# Power.net
KiCad netlist of a schematic drawn in Altium Designer
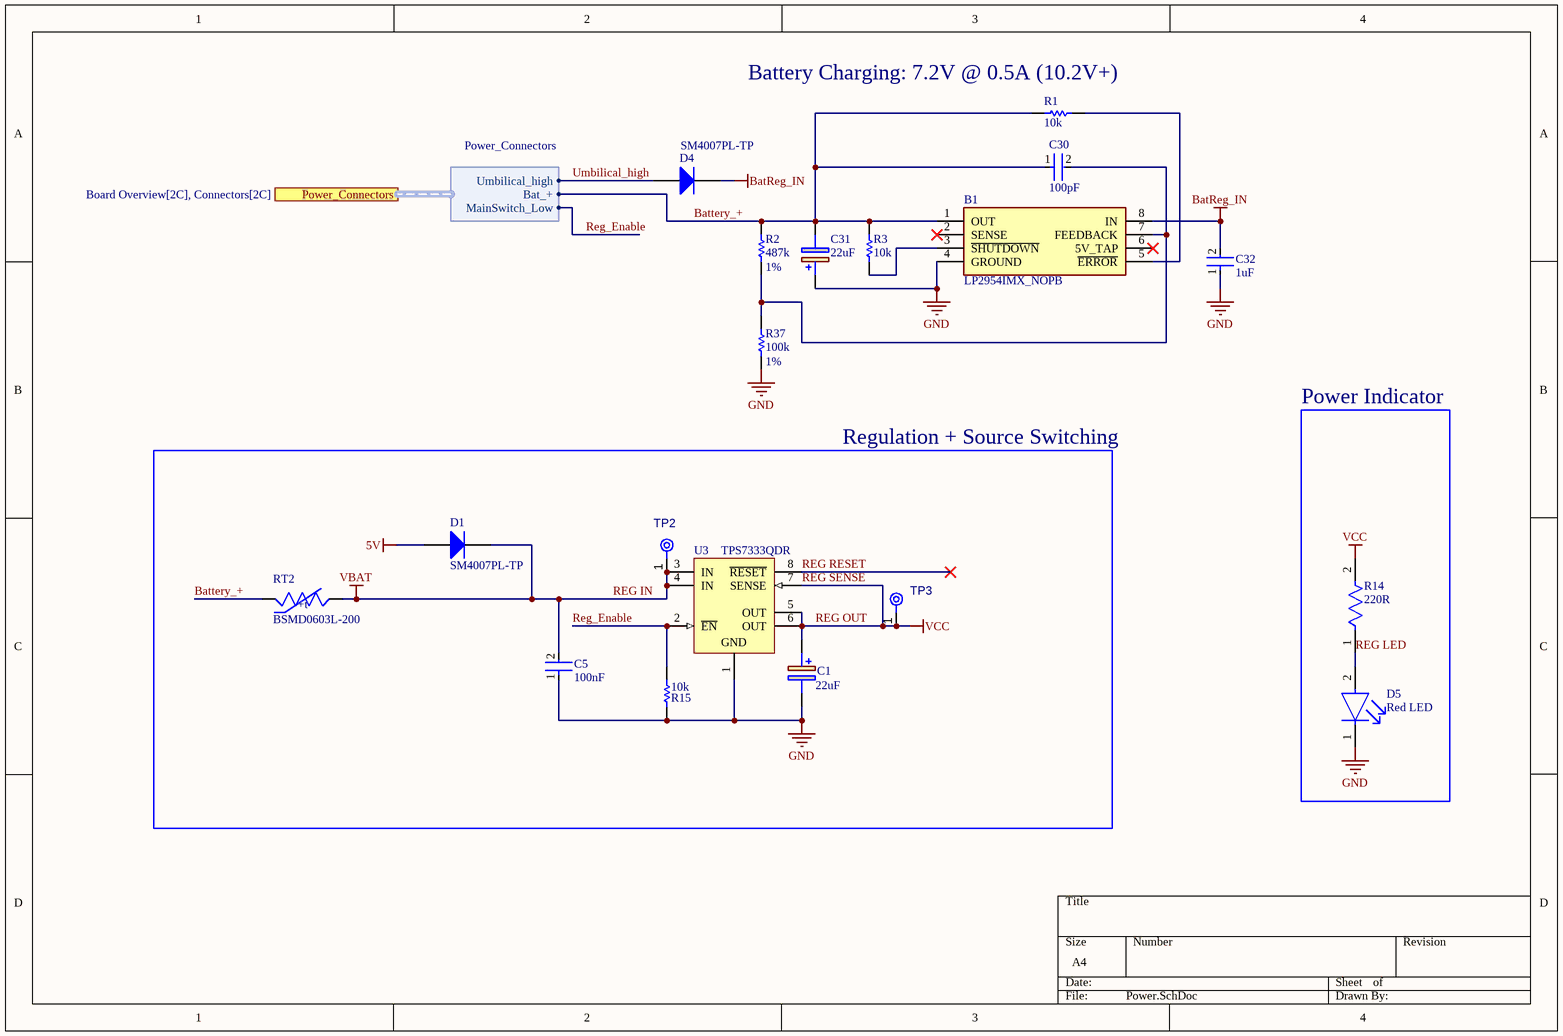
[diagram p0: Power.SchDoc]

(export (version "E")
  (design (tool "Eeschema 10.0.6"))
  (components
    (comp (ref "B1")
      (value "LP2954IMX_NOPB")
      (footprint "SOIC127P600X175-8N")
      (description "5V and Adjustable Micropower LDOs")
      (fields
        (field (name "MOUSER PART NUMBER") "926-LP2954IMX/NOPB")
        (field (name "MANUFACTURER_PART_NUMBER") "LP2954IMX/NOPB")
      )
      (libsource (lib "StrathSEDS") (part "LP2954IMX_NOPB"))
    )
    (comp (ref "C1")
      (value "TPSB226K010R0500")
      (footprint "CAPPM3528X210N")
      (description "AVX Electrolytic Capacitor 22uF 10V dc Electrolytic Solid +/-10% Tolerance TPS Series")
      (fields
        (field (name "LCSC PART #") "C400102")
        (field (name "MOUSER PART NUMBER") "581-TPSB226K010R0500")
        (field (name "CAPACITANCE") "22uF")
      )
      (libsource (lib "StrathSEDS") (part "TPSB226K010R0500"))
    )
    (comp (ref "C5")
      (value "100nF")
      (footprint "FP-0603-L_1_6_0_15-W_0_81-IPC_C")
      (description "Generic 0603 Capacitor")
      (fields (field (name "LCSC PART #") "C14663") (field (name "TOLERANCE") "10%"))
      (libsource (lib "StrathSEDS") (part "02cd4be3c70576c341d710602a673aa"))
    )
    (comp (ref "C30")
      (value "100pF")
      (footprint "FP-0603-L_1_6_0_15-W_0_81-IPC_C")
      (description "Generic 0603 Capacitor")
      (fields (field (name "LCSC PART #") "C14858") (field (name "TOLERANCE") "10%"))
      (libsource (lib "StrathSEDS") (part "02cd4be3c70576c341d710602a673aa"))
    )
    (comp (ref "C31")
      (value "TPSB226K010R0500")
      (footprint "CAPPM3528X210N")
      (description "AVX Electrolytic Capacitor 22uF 10V dc Electrolytic Solid +/-10% Tolerance TPS Series")
      (fields
        (field (name "LCSC PART #") "C400102")
        (field (name "MOUSER PART NUMBER") "581-TPSB226K010R0500")
        (field (name "CAPACITANCE") "22uF")
      )
      (libsource (lib "") (part "TPSB226K010R0500_1"))
    )
    (comp (ref "C32")
      (value "1uF")
      (footprint "FP-0603-L_1_6_0_15-W_0_81-IPC_C")
      (description "Generic 0603 Capacitor")
      (fields (field (name "LCSC PART #") "C15849") (field (name "TOLERANCE") "10%"))
      (libsource (lib "StrathSEDS") (part "02cd4be3c70576c341d710602a673aa"))
    )
    (comp (ref "D1")
      (value "SM4007PL-TP")
      (footprint "MCC-SOD-123FL_V")
      (description "DIODE GEN PURP 1KV 1A SOD123FL")
      (fields (field (name "LCSC PART #") "C64898"))
      (libsource (lib "StrathSEDS") (part "D-AK-2"))
    )
    (comp (ref "D4")
      (value "SM4007PL-TP")
      (footprint "MCC-SOD-123FL_V")
      (description "DIODE GEN PURP 1KV 1A SOD123FL")
      (fields (field (name "LCSC PART #") "C64898"))
      (libsource (lib "StrathSEDS") (part "D-AK-2"))
    )
    (comp (ref "D5")
      (value "Red LED")
      (footprint "FP-LTST-C190GKT-MFG")
      (description "SZYY0603R")
      (fields (field (name "LCSC PART #") "C434419"))
      (libsource (lib "StrathSEDS Mach 22") (part "8706943c75ba83719d021d2fdc84c58"))
    )
    (comp (ref "R1")
      (value "10k")
      (footprint "RESC1609X50X30ML8T20")
      (description "Generic 0603 Resistor")
      (fields (field (name "LCSC PART #") "C25804") (field (name "TOLERANCE") "0%"))
      (libsource (lib "StrathSEDS") (part "RES-2"))
    )
    (comp (ref "R2")
      (value "487k")
      (footprint "RESC1609X50X30ML8T20")
      (description "Generic 0603 Resistor")
      (fields
        (field (name "TOLERANCE") "1%")
        (field (name "LCSC PART #") "C2930107")
        (field (name "Comment") "Generic-Resistor")
      )
      (libsource (lib "StrathSEDS") (part "RES-2"))
    )
    (comp (ref "R3")
      (value "10k")
      (footprint "RESC1609X50X30ML8T20")
      (description "Generic 0603 Resistor")
      (fields (field (name "LCSC PART #") "C25804") (field (name "TOLERANCE") "0%"))
      (libsource (lib "StrathSEDS") (part "RES-2"))
    )
    (comp (ref "R14")
      (value "220R")
      (footprint "FP-CRCW0603-e3-IPC_C")
      (description "Res Thick Film 0603 220 Ohm 1% 1/10W ±100ppm/°C Molded SMD SMD Paper T/R")
      (fields (field (name "LCSC PART #") "C22962"))
      (libsource (lib "StrathSEDS Mach 22") (part "1029c3af85768c4190bb7ad29bc67b5"))
    )
    (comp (ref "R15")
      (value "10k")
      (footprint "RESC1608X55X25ML10T15")
      (fields (field (name "LCSC PART #") "C25804"))
      (libsource (lib "StrathSEDS Mach 22") (part "RES-2"))
    )
    (comp (ref "R37")
      (value "100k")
      (footprint "RESC1609X50X30ML8T20")
      (description "Generic 0603 Resistor")
      (fields
        (field (name "TOLERANCE") "1%")
        (field (name "LCSC PART #") "C25803")
        (field (name "Comment") "Generic-Resistor")
      )
      (libsource (lib "StrathSEDS") (part "RES-2"))
    )
    (comp (ref "RT2")
      (value "BSMD0603L-200")
      (footprint "THRMC1608X95N")
      (description "PTC Resettable Fuse: 2A Hold, 4A Trip, 0603")
      (fields (field (name "LCSC PART #") "C2757930"))
      (libsource (lib "StrathSEDS") (part "BSMD0603L-200"))
    )
    (comp (ref "TP2")
      (value "TPAD6R")
      (footprint "TP06R")
      (description "0.6mm round")
      (libsource (lib "StrathSEDS") (part "CMP-001-0001-4"))
    )
    (comp (ref "TP3")
      (value "TPAD6R")
      (footprint "TP06R")
      (description "0.6mm round")
      (libsource (lib "StrathSEDS") (part "CMP-001-0001-4"))
    )
    (comp (ref "U3")
      (value "TPS7333QDR")
      (footprint "D0008A_L")
      (description "IC REG LDO 3.3V 0.5A 8SOIC")
      (fields (field (name "LCSC PART #") "C23791"))
      (libsource (lib "StrathSEDS Mach 22") (part "TI-TPS73XX-8"))
    )
  )
  (nets
    (net (code "2") (name "/Battery_+") (class "Default")
      (node (ref "B1") (pin "1") (pinfunction "OUT_1") (pintype "passive"))
      (node (ref "C30") (pin "1") (pinfunction "1_1") (pintype "passive"))
      (node (ref "C31") (pin "2") (pinfunction "-_2") (pintype "passive"))
      (node (ref "R1") (pin "1") (pinfunction "1_1") (pintype "passive"))
      (node (ref "R2") (pin "1") (pinfunction "1_1") (pintype "passive"))
      (node (ref "R3") (pin "2") (pinfunction "2_2") (pintype "passive"))
      (node (ref "RT2") (pin "1") (pinfunction "1_1") (pintype "passive"))
    )
    (net (code "3") (name "/REG LED") (class "Default")
      (node (ref "D5") (pin "2") (pinfunction "A_2") (pintype "passive"))
      (node (ref "R14") (pin "1") (pinfunction "1_1") (pintype "passive"))
    )
    (net (code "4") (name "/REG RESET") (class "Default")
      (node (ref "U3") (pin "8") (pinfunction "~{RESET}_8") (pintype "open_collector+no_connect"))
    )
    (net (code "5") (name "/Reg_Enable") (class "Default")
      (node (ref "R15") (pin "2") (pinfunction "2_2") (pintype "passive"))
      (node (ref "U3") (pin "2") (pinfunction "~{EN}_2") (pintype "input"))
    )
    (net (code "6") (name "/Umbilical_high") (class "Default")
      (node (ref "D4") (pin "1") (pinfunction "A_1") (pintype "passive"))
    )
    (net (code "8") (name "5V") (class "Default")
      (node (ref "D1") (pin "1") (pinfunction "A_1") (pintype "passive"))
    )
    (net (code "9") (name "BatReg_IN") (class "Default")
      (node (ref "B1") (pin "8") (pinfunction "IN_8") (pintype "passive"))
      (node (ref "C32") (pin "2") (pinfunction "2_2") (pintype "passive"))
      (node (ref "D4") (pin "2") (pinfunction "K_2") (pintype "passive"))
    )
    (net (code "10") (name "GND") (class "Default")
      (node (ref "B1") (pin "4") (pinfunction "GROUND_4") (pintype "passive"))
      (node (ref "C1") (pin "2") (pinfunction "-_2") (pintype "passive"))
      (node (ref "C31") (pin "1") (pinfunction "+_1") (pintype "passive"))
      (node (ref "C32") (pin "1") (pinfunction "1_1") (pintype "passive"))
      (node (ref "C5") (pin "1") (pinfunction "1_1") (pintype "passive"))
      (node (ref "D5") (pin "1") (pinfunction "C_1") (pintype "passive"))
      (node (ref "R15") (pin "1") (pinfunction "1_1") (pintype "passive"))
      (node (ref "R37") (pin "2") (pinfunction "2_2") (pintype "passive"))
      (node (ref "U3") (pin "1") (pinfunction "GND_1") (pintype "power_in"))
    )
    (net (code "11") (name "Net-(B1-FEEDBACK)") (class "Default")
      (node (ref "B1") (pin "7") (pinfunction "FEEDBACK_7") (pintype "passive"))
      (node (ref "C30") (pin "2") (pinfunction "2_2") (pintype "passive"))
      (node (ref "R2") (pin "2") (pinfunction "2_2") (pintype "passive"))
      (node (ref "R37") (pin "1") (pinfunction "1_1") (pintype "passive"))
    )
    (net (code "12") (name "Net-(B1-~{ERROR})") (class "Default")
      (node (ref "B1") (pin "5") (pinfunction "~{ERROR}_5") (pintype "passive"))
      (node (ref "R1") (pin "2") (pinfunction "2_2") (pintype "passive"))
    )
    (net (code "13") (name "Net-(B1-~{SHUTDOWN})") (class "Default")
      (node (ref "B1") (pin "3") (pinfunction "~{SHUTDOWN}_3") (pintype "passive"))
      (node (ref "R3") (pin "1") (pinfunction "1_1") (pintype "passive"))
    )
    (net (code "14") (name "VBAT") (class "Default")
      (node (ref "C5") (pin "2") (pinfunction "2_2") (pintype "passive"))
      (node (ref "D1") (pin "2") (pinfunction "K_2") (pintype "passive"))
      (node (ref "RT2") (pin "2") (pinfunction "2_2") (pintype "passive"))
      (node (ref "TP2") (pin "1") (pinfunction "TP_1") (pintype "passive"))
      (node (ref "U3") (pin "3") (pinfunction "IN_3") (pintype "power_in"))
      (node (ref "U3") (pin "4") (pinfunction "IN_4") (pintype "power_in"))
    )
    (net (code "15") (name "VCC") (class "Default")
      (node (ref "C1") (pin "1") (pinfunction "+_1") (pintype "passive"))
      (node (ref "R14") (pin "2") (pinfunction "2_2") (pintype "passive"))
      (node (ref "TP3") (pin "1") (pinfunction "TP_1") (pintype "passive"))
      (node (ref "U3") (pin "5") (pinfunction "OUT_5") (pintype "power_in"))
      (node (ref "U3") (pin "6") (pinfunction "OUT_6") (pintype "power_in"))
      (node (ref "U3") (pin "7") (pinfunction "SENSE_7") (pintype "input"))
    )
    (net (code "16") (name "unconnected-(B1-5V_TAP-Pad6)") (class "Default")
      (node (ref "B1") (pin "6") (pinfunction "5V_TAP_6") (pintype "passive+no_connect"))
    )
    (net (code "17") (name "unconnected-(B1-SENSE-Pad2)") (class "Default")
      (node (ref "B1") (pin "2") (pinfunction "SENSE_2") (pintype "passive+no_connect"))
    )
  )
)
